# mpu-9250.net
KiCad netlist of a schematic drawn in EAGLE
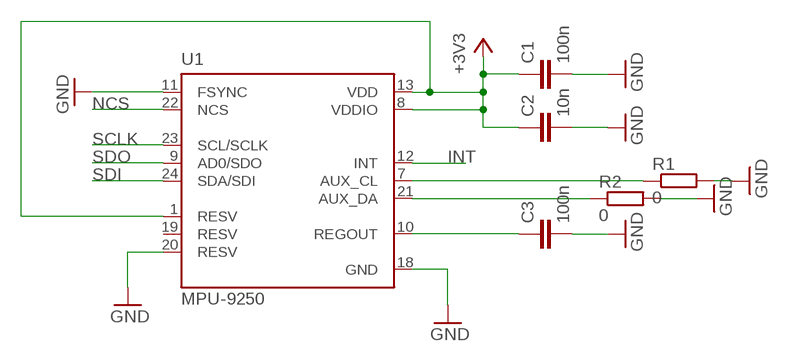
[diagram p0: schematic, sheet 1]

(export (version "E")
  (design (tool "Eeschema 10.0.6"))
  (components
    (comp (ref "C1")
      (value "100n")
      (footprint "eagle-import:C0805")
      (libsource (lib "eagle-import") (part "C-EUC0805"))
    )
    (comp (ref "C2")
      (value "10n")
      (footprint "eagle-import:C0805")
      (libsource (lib "eagle-import") (part "C-EUC0805"))
    )
    (comp (ref "C3")
      (value "100n")
      (footprint "eagle-import:C0805")
      (libsource (lib "eagle-import") (part "C-EUC0805"))
    )
    (comp (ref "R1")
      (value "0")
      (footprint "eagle-import:R0805")
      (libsource (lib "eagle-import") (part "R-EU_R0805"))
    )
    (comp (ref "R2")
      (value "0")
      (footprint "eagle-import:R0805")
      (libsource (lib "eagle-import") (part "R-EU_R0805"))
    )
    (comp (ref "U1")
      (value "MPU-9250")
      (footprint "eagle-import:QFN40P300X300X105-25N")
      (fields (field (name "MF") "InvenSense"))
      (libsource (lib "eagle-import") (part "MPU-9250"))
    )
  )
  (nets
    (net (code "1") (name "+3V3") (class "Default")
      (node (ref "C1") (pin "1") (pinfunction "1_1") (pintype "passive"))
      (node (ref "C2") (pin "1") (pinfunction "1_1") (pintype "passive"))
      (node (ref "U1") (pin "1") (pinfunction "RESV_1") (pintype "power_in"))
      (node (ref "U1") (pin "13") (pinfunction "VDD_13") (pintype "power_in"))
      (node (ref "U1") (pin "8") (pinfunction "VDDIO_8") (pintype "power_in"))
    )
    (net (code "2") (name "/INT") (class "Default")
      (node (ref "U1") (pin "12") (pinfunction "INT_12") (pintype "output"))
    )
    (net (code "3") (name "/NCS") (class "Default")
      (node (ref "U1") (pin "22") (pinfunction "NCS_22") (pintype "input"))
    )
    (net (code "4") (name "/RESV") (class "Default")
      (node (ref "U1") (pin "19") (pinfunction "RESV_19") (pintype "power_in"))
    )
    (net (code "5") (name "/SCLK") (class "Default")
      (node (ref "U1") (pin "23") (pinfunction "SCL/SCLK_23") (pintype "input"))
    )
    (net (code "6") (name "/SDI") (class "Default")
      (node (ref "U1") (pin "24") (pinfunction "SDA/SDI_24") (pintype "bidirectional"))
    )
    (net (code "7") (name "/SDO") (class "Default")
      (node (ref "U1") (pin "9") (pinfunction "AD0/SDO_9") (pintype "bidirectional"))
    )
    (net (code "8") (name "GND") (class "Default")
      (node (ref "C1") (pin "2") (pinfunction "2_2") (pintype "passive"))
      (node (ref "C2") (pin "2") (pinfunction "2_2") (pintype "passive"))
      (node (ref "C3") (pin "2") (pinfunction "2_2") (pintype "passive"))
      (node (ref "R1") (pin "2") (pinfunction "2_2") (pintype "passive"))
      (node (ref "R2") (pin "2") (pinfunction "2_2") (pintype "passive"))
      (node (ref "U1") (pin "11") (pinfunction "FSYNC_11") (pintype "input"))
      (node (ref "U1") (pin "18") (pinfunction "GND_18") (pintype "power_in"))
      (node (ref "U1") (pin "20") (pinfunction "RESV_20") (pintype "power_in"))
    )
    (net (code "9") (name "Net-(U1-AUX_CL)") (class "Default")
      (node (ref "R1") (pin "1") (pinfunction "1_1") (pintype "passive"))
      (node (ref "U1") (pin "7") (pinfunction "AUX_CL_7") (pintype "output"))
    )
    (net (code "10") (name "Net-(U1-AUX_DA)") (class "Default")
      (node (ref "R2") (pin "1") (pinfunction "1_1") (pintype "passive"))
      (node (ref "U1") (pin "21") (pinfunction "AUX_DA_21") (pintype "output"))
    )
    (net (code "11") (name "Net-(U1-REGOUT)") (class "Default")
      (node (ref "C3") (pin "1") (pinfunction "1_1") (pintype "passive"))
      (node (ref "U1") (pin "10") (pinfunction "REGOUT_10") (pintype "passive"))
    )
  )
)
